# Anchor_PCB_V2.net
KiCad netlist of a schematic drawn in EAGLE
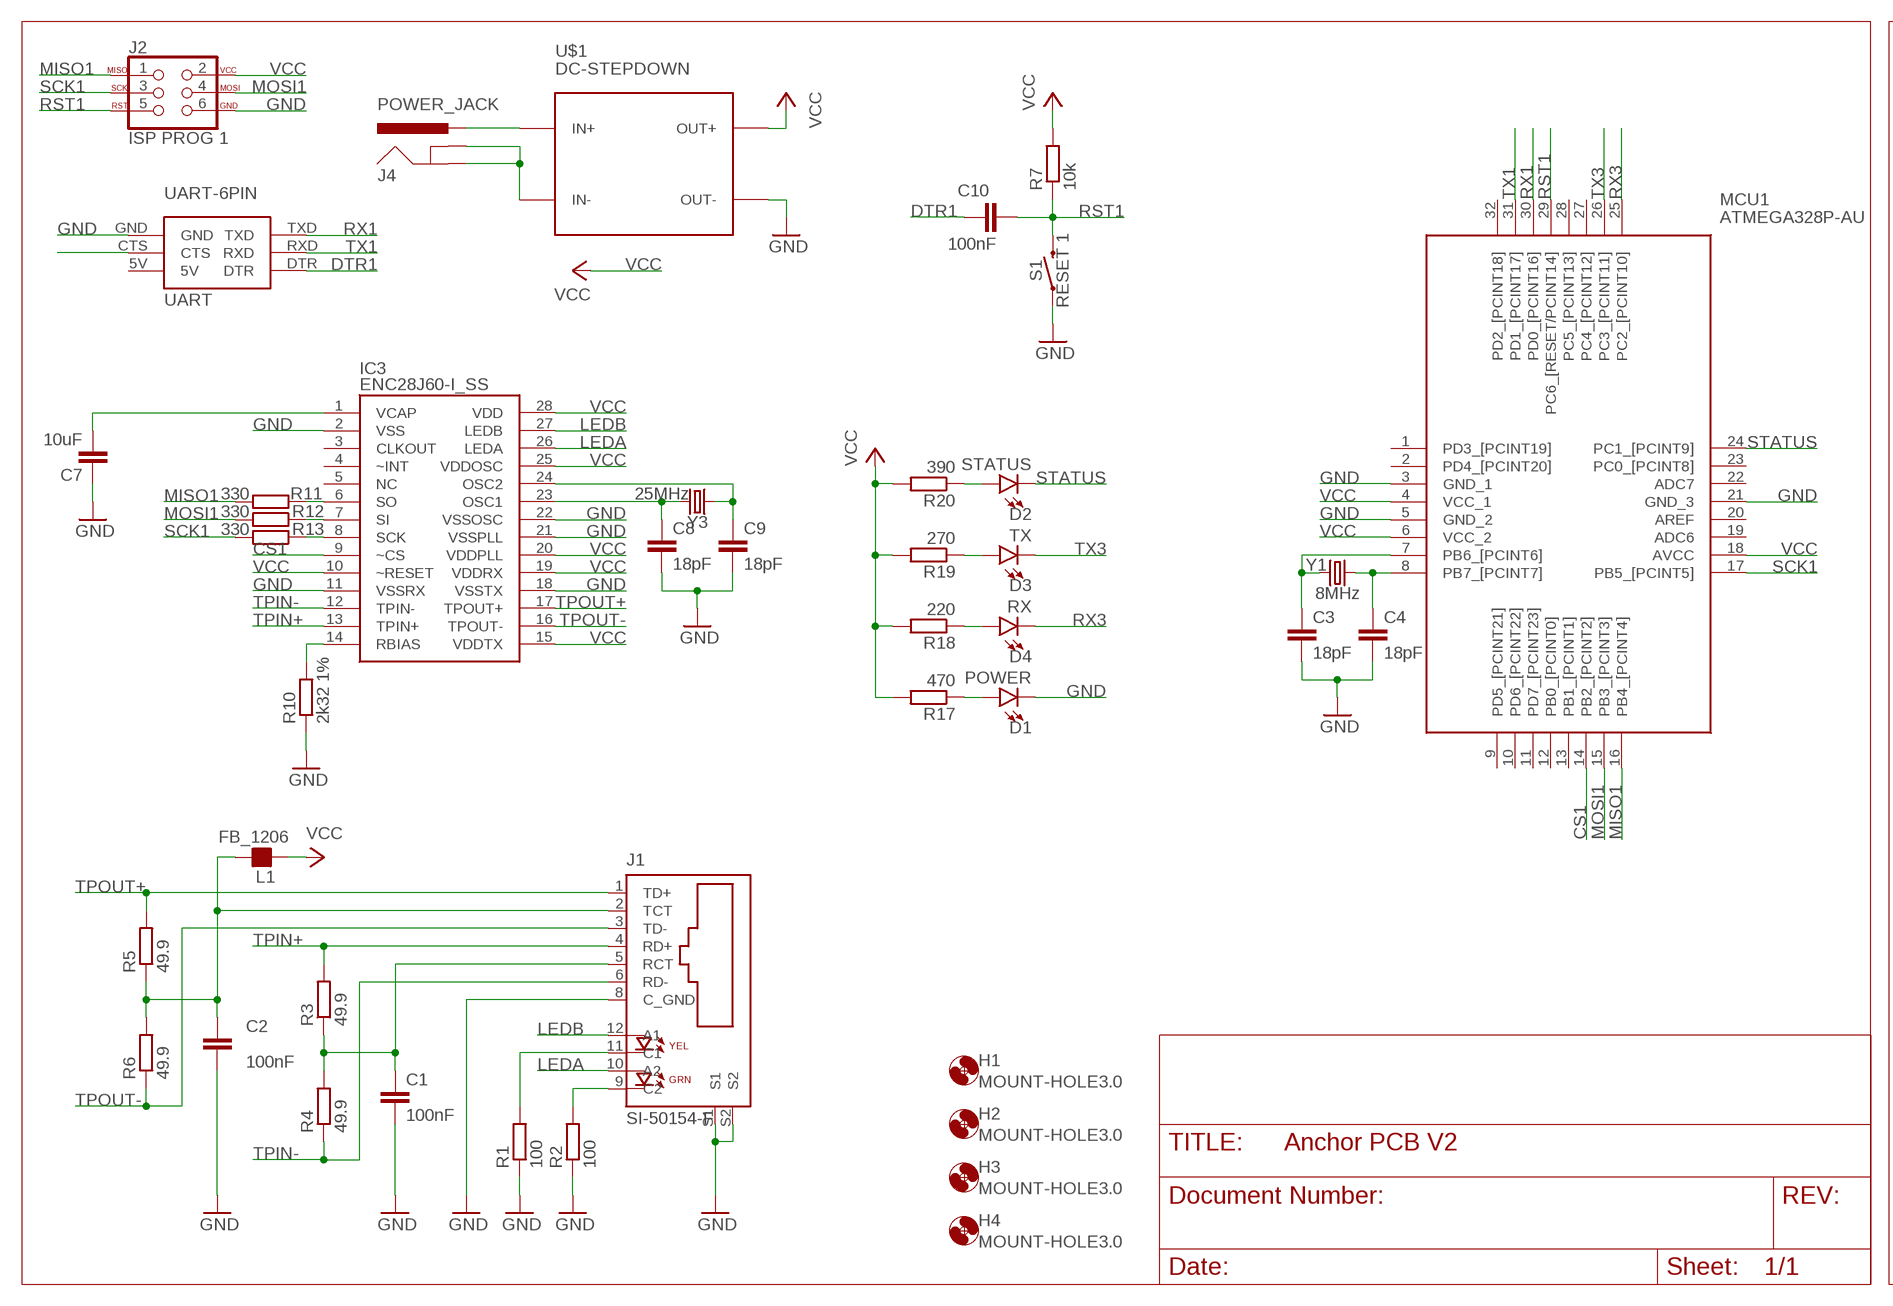
[diagram p0: schematic, sheet 1, part 1 of 2]
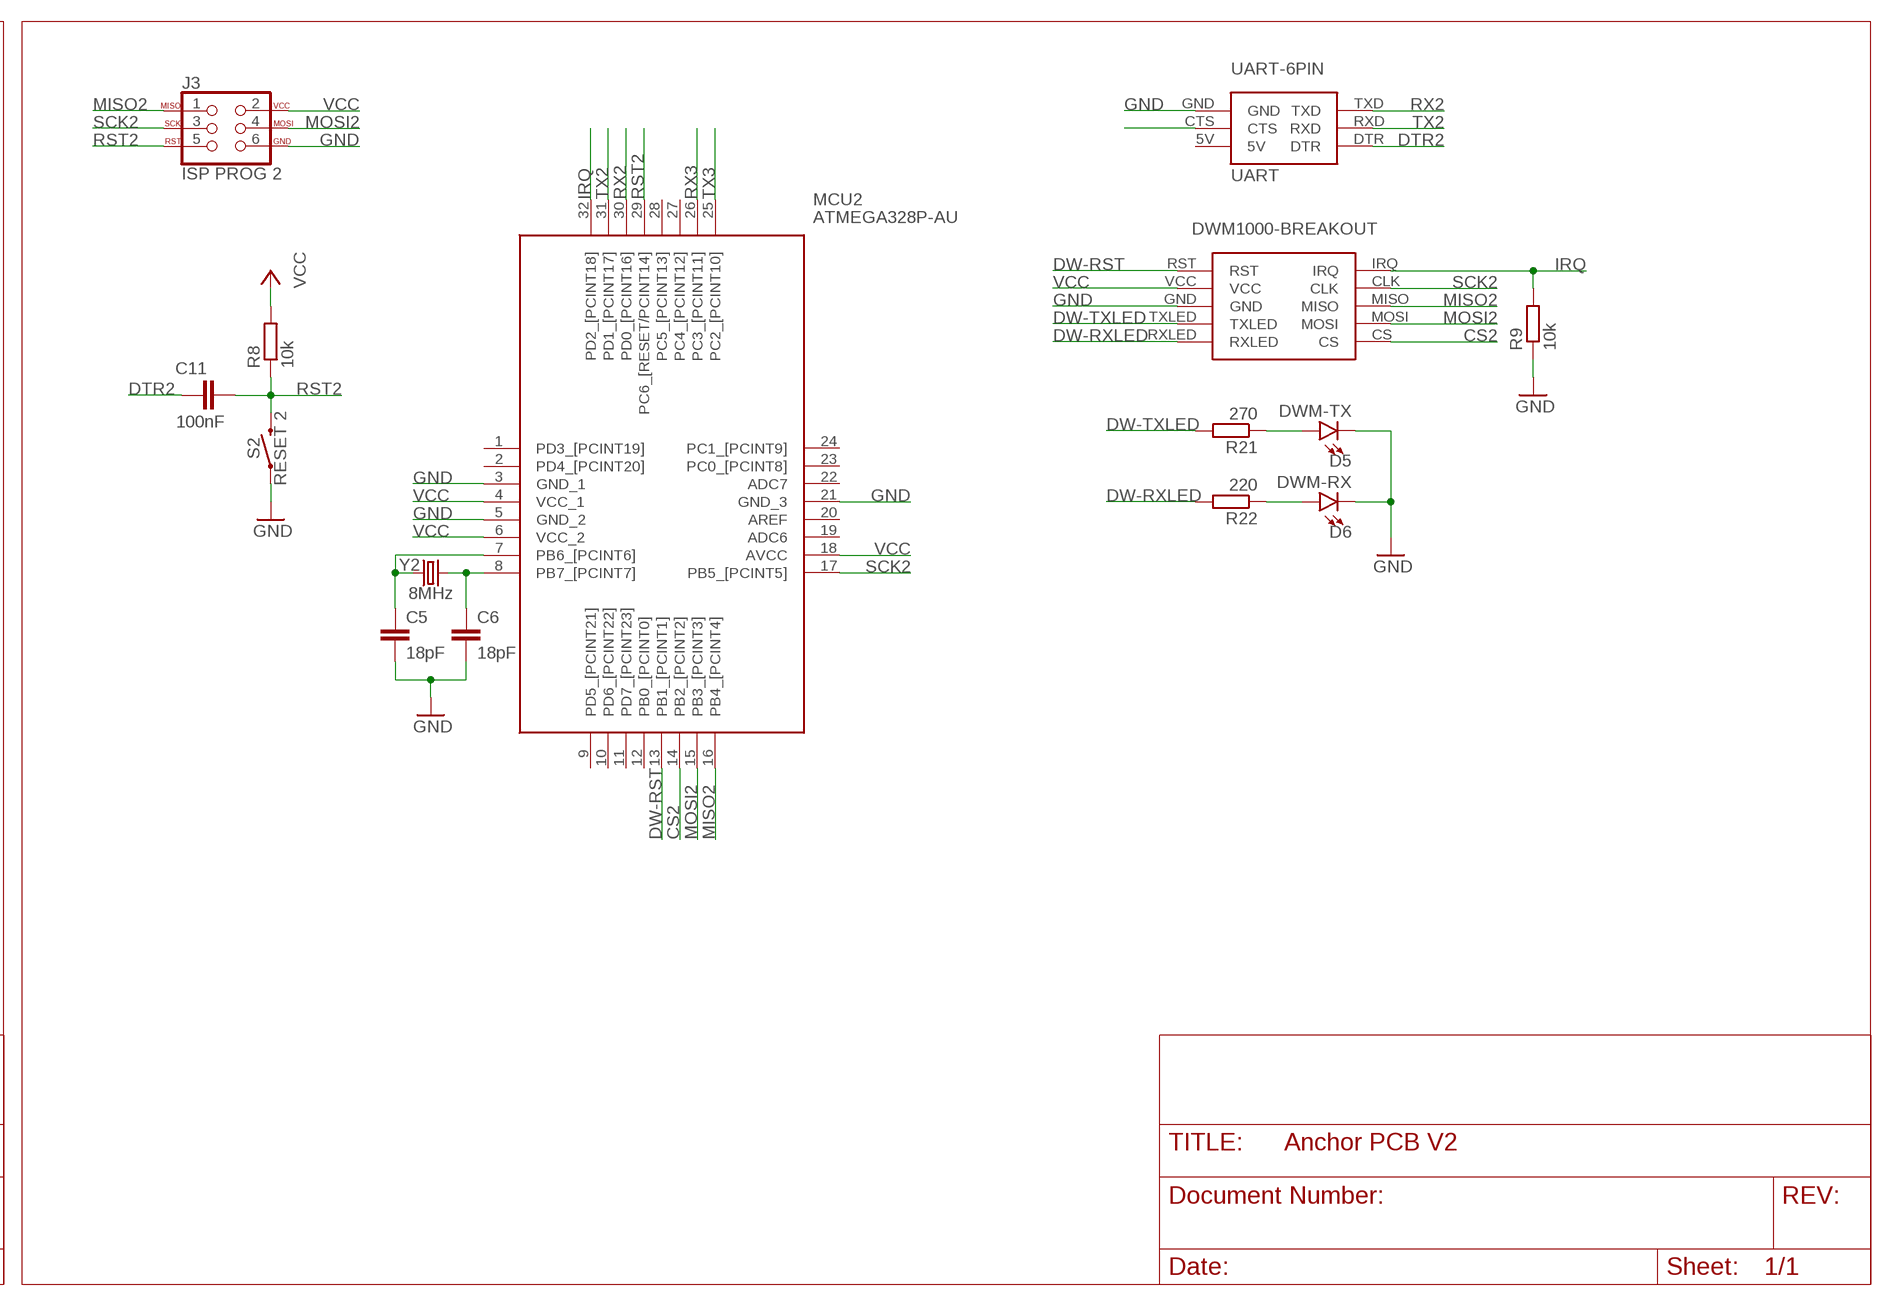
[diagram p1: schematic, sheet 1, part 2 of 2]

(export (version "E")
  (design (tool "Eeschema 10.0.6"))
  (components
    (comp (ref "C1")
      (value "100nF")
      (footprint "eagle-import:C0805")
      (libsource (lib "eagle-import") (part "C-EUC0805"))
    )
    (comp (ref "C2")
      (value "100nF")
      (footprint "eagle-import:C0805")
      (libsource (lib "eagle-import") (part "C-EUC0805"))
    )
    (comp (ref "C3")
      (value "18pF")
      (footprint "eagle-import:C0805")
      (libsource (lib "eagle-import") (part "C-EUC0805"))
    )
    (comp (ref "C4")
      (value "18pF")
      (footprint "eagle-import:C0805")
      (libsource (lib "eagle-import") (part "C-EUC0805"))
    )
    (comp (ref "C5")
      (value "18pF")
      (footprint "eagle-import:C0805")
      (libsource (lib "eagle-import") (part "C-EUC0805"))
    )
    (comp (ref "C6")
      (value "18pF")
      (footprint "eagle-import:C0805")
      (libsource (lib "eagle-import") (part "C-EUC0805"))
    )
    (comp (ref "C7")
      (value "10uF")
      (footprint "eagle-import:C0805")
      (libsource (lib "eagle-import") (part "C-EUC0805"))
    )
    (comp (ref "C8")
      (value "18pF")
      (footprint "eagle-import:C0805")
      (libsource (lib "eagle-import") (part "C-EUC0805"))
    )
    (comp (ref "C9")
      (value "18pF")
      (footprint "eagle-import:C0805")
      (libsource (lib "eagle-import") (part "C-EUC0805"))
    )
    (comp (ref "C10")
      (value "100nF")
      (footprint "eagle-import:C0805")
      (libsource (lib "eagle-import") (part "C-EUC0805"))
    )
    (comp (ref "C11")
      (value "100nF")
      (footprint "eagle-import:C0805")
      (libsource (lib "eagle-import") (part "C-EUC0805"))
    )
    (comp (ref "D1")
      (value "POWER")
      (footprint "eagle-import:LED-1206")
      (libsource (lib "eagle-import") (part "LED-BLUE1206"))
    )
    (comp (ref "D2")
      (value "STATUS")
      (footprint "eagle-import:LED-1206")
      (fields (field (name "SPICEPREFIX") "D"))
      (libsource (lib "eagle-import") (part "LED-RED1206"))
    )
    (comp (ref "D3")
      (value "TX")
      (footprint "eagle-import:LED-1206")
      (fields (field (name "SPICEPREFIX") "D"))
      (libsource (lib "eagle-import") (part "LED-YELLOWLILYPAD"))
    )
    (comp (ref "D4")
      (value "RX")
      (footprint "eagle-import:LED-1206")
      (fields (field (name "SPICEPREFIX") "D"))
      (libsource (lib "eagle-import") (part "LED-GREEN1206"))
    )
    (comp (ref "D5")
      (value "DWM-TX")
      (footprint "eagle-import:LED-1206")
      (fields (field (name "SPICEPREFIX") "D"))
      (libsource (lib "eagle-import") (part "LED-YELLOWLILYPAD"))
    )
    (comp (ref "D6")
      (value "DWM-RX")
      (footprint "eagle-import:LED-1206")
      (fields (field (name "SPICEPREFIX") "D"))
      (libsource (lib "eagle-import") (part "LED-GREEN1206"))
    )
    (comp (ref "H1")
      (value "MOUNT-HOLE3.0")
      (footprint "eagle-import:3,0")
      (libsource (lib "eagle-import") (part "MOUNT-HOLE3.0"))
    )
    (comp (ref "H2")
      (value "MOUNT-HOLE3.0")
      (footprint "eagle-import:3,0")
      (libsource (lib "eagle-import") (part "MOUNT-HOLE3.0"))
    )
    (comp (ref "H3")
      (value "MOUNT-HOLE3.0")
      (footprint "eagle-import:3,0")
      (libsource (lib "eagle-import") (part "MOUNT-HOLE3.0"))
    )
    (comp (ref "H4")
      (value "MOUNT-HOLE3.0")
      (footprint "eagle-import:3,0")
      (libsource (lib "eagle-import") (part "MOUNT-HOLE3.0"))
    )
    (comp (ref "IC3")
      (value "ENC28J60-I_SS")
      (footprint "eagle-import:SOP65P780X200-28N")
      (fields (field (name "ARROW_PART_NUMBER") "ENC28J60-I/SS") (field (name "RS_PART_NUMBER") "7707755P"))
      (libsource (lib "eagle-import") (part "ENC28J60-I_SS"))
    )
    (comp (ref "J1")
      (value "SI-50154-F")
      (footprint "eagle-import:STEWART_SI-50154-F")
      (fields (field (name "MF") "Stewart Connector"))
      (libsource (lib "eagle-import") (part "SI-50154-F"))
    )
    (comp (ref "J2")
      (value "ISP PROG 1")
      (footprint "eagle-import:2X3")
      (libsource (lib "eagle-import") (part "AVR_SPI_PROG_3X2PTH"))
    )
    (comp (ref "J3")
      (value "ISP PROG 2")
      (footprint "eagle-import:2X3")
      (libsource (lib "eagle-import") (part "AVR_SPI_PROG_3X2PTH"))
    )
    (comp (ref "J4")
      (value "POWER_JACK")
      (footprint "eagle-import:POWER_JACK_PTH")
      (libsource (lib "eagle-import") (part "POWER_JACK"))
    )
    (comp (ref "L1")
      (value "FB_1206")
      (footprint "eagle-import:L1206")
      (libsource (lib "eagle-import") (part "FB_1206"))
    )
    (comp (ref "MCU1")
      (value "ATMEGA328P-AU")
      (footprint "eagle-import:QFP80P900X900X120-32N")
      (fields (field (name "RS_PART_NUMBER") "1310271"))
      (libsource (lib "eagle-import") (part "ATMEGA328P-AU"))
    )
    (comp (ref "MCU2")
      (value "ATMEGA328P-AU")
      (footprint "eagle-import:QFP80P900X900X120-32N")
      (fields (field (name "RS_PART_NUMBER") "1310271"))
      (libsource (lib "eagle-import") (part "ATMEGA328P-AU"))
    )
    (comp (ref "R1")
      (value "100")
      (footprint "eagle-import:R0805")
      (libsource (lib "eagle-import") (part "R-EU_R0805"))
    )
    (comp (ref "R2")
      (value "100")
      (footprint "eagle-import:R0805")
      (libsource (lib "eagle-import") (part "R-EU_R0805"))
    )
    (comp (ref "R3")
      (value "49.9")
      (footprint "eagle-import:R1206")
      (libsource (lib "eagle-import") (part "R-EU_R1206"))
    )
    (comp (ref "R4")
      (value "49.9")
      (footprint "eagle-import:R1206")
      (libsource (lib "eagle-import") (part "R-EU_R1206"))
    )
    (comp (ref "R5")
      (value "49.9")
      (footprint "eagle-import:R1206")
      (libsource (lib "eagle-import") (part "R-EU_R1206"))
    )
    (comp (ref "R6")
      (value "49.9")
      (footprint "eagle-import:R1206")
      (libsource (lib "eagle-import") (part "R-EU_R1206"))
    )
    (comp (ref "R7")
      (value "10k")
      (footprint "eagle-import:R0805")
      (libsource (lib "eagle-import") (part "R-EU_R0805"))
    )
    (comp (ref "R8")
      (value "10k")
      (footprint "eagle-import:R0805")
      (libsource (lib "eagle-import") (part "R-EU_R0805"))
    )
    (comp (ref "R9")
      (value "10k")
      (footprint "eagle-import:R0805")
      (libsource (lib "eagle-import") (part "R-EU_R0805"))
    )
    (comp (ref "R10")
      (value "2k32 1%")
      (footprint "eagle-import:R1206")
      (libsource (lib "eagle-import") (part "R-EU_R1206"))
    )
    (comp (ref "R11")
      (value "330")
      (footprint "eagle-import:R0805")
      (libsource (lib "eagle-import") (part "R-EU_R0805"))
    )
    (comp (ref "R12")
      (value "330")
      (footprint "eagle-import:R0805")
      (libsource (lib "eagle-import") (part "R-EU_R0805"))
    )
    (comp (ref "R13")
      (value "330")
      (footprint "eagle-import:R0805")
      (libsource (lib "eagle-import") (part "R-EU_R0805"))
    )
    (comp (ref "R17")
      (value "470")
      (footprint "eagle-import:R1206")
      (libsource (lib "eagle-import") (part "R-EU_R1206"))
    )
    (comp (ref "R18")
      (value "220")
      (footprint "eagle-import:R1206")
      (libsource (lib "eagle-import") (part "R-EU_R1206"))
    )
    (comp (ref "R19")
      (value "270")
      (footprint "eagle-import:R1206")
      (libsource (lib "eagle-import") (part "R-EU_R1206"))
    )
    (comp (ref "R20")
      (value "390")
      (footprint "eagle-import:R1206")
      (libsource (lib "eagle-import") (part "R-EU_R1206"))
    )
    (comp (ref "R21")
      (value "270")
      (footprint "eagle-import:R1206")
      (libsource (lib "eagle-import") (part "R-EU_R1206"))
    )
    (comp (ref "R22")
      (value "220")
      (footprint "eagle-import:R1206")
      (libsource (lib "eagle-import") (part "R-EU_R1206"))
    )
    (comp (ref "S1")
      (value "RESET 1")
      (footprint "eagle-import:TACTILE_SWITCH_PTH_6.0MM")
      (libsource (lib "eagle-import") (part "MOMENTARY-SWITCH-SPST-PTH-6.0MM"))
    )
    (comp (ref "S2")
      (value "RESET 2")
      (footprint "eagle-import:TACTILE_SWITCH_PTH_6.0MM")
      (libsource (lib "eagle-import") (part "MOMENTARY-SWITCH-SPST-PTH-6.0MM"))
    )
    (comp (ref "U$1")
      (value "DC-STEPDOWN")
      (footprint "eagle-import:DC-DC-STEP-DOWN-LM2596")
      (libsource (lib "eagle-import") (part "DC-DC-STEP-DOWN-LM2596"))
    )
    (comp (ref "U$2")
      (value "DWM1000")
      (footprint "eagle-import:DWM1000-BREAKOUT")
      (libsource (lib "eagle-import") (part "DWM1000-BREAKOUT"))
    )
    (comp (ref "UART1")
      (value "UART1")
      (footprint "eagle-import:UART-6PIN")
      (libsource (lib "eagle-import") (part "UART-6PIN"))
    )
    (comp (ref "UART2")
      (value "UART2")
      (footprint "eagle-import:UART-6PIN")
      (libsource (lib "eagle-import") (part "UART-6PIN"))
    )
    (comp (ref "Y1")
      (value "8MHz")
      (footprint "eagle-import:HC49UP")
      (libsource (lib "eagle-import") (part "CRYSTALSMD-HC49UP"))
    )
    (comp (ref "Y2")
      (value "8MHz")
      (footprint "eagle-import:HC49UP")
      (libsource (lib "eagle-import") (part "CRYSTALSMD-HC49UP"))
    )
    (comp (ref "Y3")
      (value "25MHz")
      (footprint "eagle-import:HC49UP")
      (libsource (lib "eagle-import") (part "CRYSTALSMD-HC49UP"))
    )
  )
  (nets
    (net (code "1") (name "/CS1") (class "Default")
      (node (ref "IC3") (pin "9") (pinfunction "~{CS}_9") (pintype "bidirectional"))
      (node (ref "MCU1") (pin "14") (pinfunction "PB2_[PCINT2]_14") (pintype "bidirectional"))
    )
    (net (code "2") (name "/CS2") (class "Default")
      (node (ref "MCU2") (pin "14") (pinfunction "PB2_[PCINT2]_14") (pintype "bidirectional"))
      (node (ref "U$2") (pin "CS") (pinfunction "CS_CS") (pintype "bidirectional"))
    )
    (net (code "3") (name "/DTR1") (class "Default")
      (node (ref "C10") (pin "1") (pinfunction "1_1") (pintype "passive"))
      (node (ref "UART1") (pin "DTR") (pinfunction "DTR_DTR") (pintype "bidirectional"))
    )
    (net (code "4") (name "/DTR2") (class "Default")
      (node (ref "C11") (pin "1") (pinfunction "1_1") (pintype "passive"))
      (node (ref "UART2") (pin "DTR") (pinfunction "DTR_DTR") (pintype "bidirectional"))
    )
    (net (code "5") (name "/DW-RST") (class "Default")
      (node (ref "MCU2") (pin "13") (pinfunction "PB1_[PCINT1]_13") (pintype "bidirectional"))
      (node (ref "U$2") (pin "RST") (pinfunction "RST_RST") (pintype "bidirectional"))
    )
    (net (code "6") (name "/DW-RXLED") (class "Default")
      (node (ref "R22") (pin "2") (pinfunction "2_2") (pintype "passive"))
      (node (ref "U$2") (pin "RXLED") (pinfunction "RXLED_RXLED") (pintype "bidirectional"))
    )
    (net (code "7") (name "/DW-TXLED") (class "Default")
      (node (ref "R21") (pin "2") (pinfunction "2_2") (pintype "passive"))
      (node (ref "U$2") (pin "TXLED") (pinfunction "TXLED_TXLED") (pintype "bidirectional"))
    )
    (net (code "8") (name "/IRQ") (class "Default")
      (node (ref "MCU2") (pin "32") (pinfunction "PD2_[PCINT18]_32") (pintype "bidirectional"))
      (node (ref "R9") (pin "2") (pinfunction "2_2") (pintype "passive"))
      (node (ref "U$2") (pin "IRQ") (pinfunction "IRQ_IRQ") (pintype "bidirectional"))
    )
    (net (code "9") (name "/LEDA") (class "Default")
      (node (ref "IC3") (pin "26") (pinfunction "LEDA_26") (pintype "bidirectional"))
      (node (ref "J1") (pin "10") (pinfunction "A2_10") (pintype "passive"))
    )
    (net (code "10") (name "/LEDB") (class "Default")
      (node (ref "IC3") (pin "27") (pinfunction "LEDB_27") (pintype "bidirectional"))
      (node (ref "J1") (pin "12") (pinfunction "A1_12") (pintype "passive"))
    )
    (net (code "11") (name "/MISO1") (class "Default")
      (node (ref "J2") (pin "1") (pinfunction "1_1") (pintype "passive"))
      (node (ref "MCU1") (pin "16") (pinfunction "PB4_[PCINT4]_16") (pintype "bidirectional"))
      (node (ref "R11") (pin "2") (pinfunction "2_2") (pintype "passive"))
    )
    (net (code "12") (name "/MISO2") (class "Default")
      (node (ref "J3") (pin "1") (pinfunction "1_1") (pintype "passive"))
      (node (ref "MCU2") (pin "16") (pinfunction "PB4_[PCINT4]_16") (pintype "bidirectional"))
      (node (ref "U$2") (pin "MISO") (pinfunction "MISO_MISO") (pintype "bidirectional"))
    )
    (net (code "13") (name "/MOSI1") (class "Default")
      (node (ref "J2") (pin "4") (pinfunction "4_4") (pintype "passive"))
      (node (ref "MCU1") (pin "15") (pinfunction "PB3_[PCINT3]_15") (pintype "bidirectional"))
      (node (ref "R12") (pin "2") (pinfunction "2_2") (pintype "passive"))
    )
    (net (code "14") (name "/MOSI2") (class "Default")
      (node (ref "J3") (pin "4") (pinfunction "4_4") (pintype "passive"))
      (node (ref "MCU2") (pin "15") (pinfunction "PB3_[PCINT3]_15") (pintype "bidirectional"))
      (node (ref "U$2") (pin "MOSI") (pinfunction "MOSI_MOSI") (pintype "bidirectional"))
    )
    (net (code "15") (name "/RST1") (class "Default")
      (node (ref "C10") (pin "2") (pinfunction "2_2") (pintype "passive"))
      (node (ref "J2") (pin "5") (pinfunction "5_5") (pintype "passive"))
      (node (ref "MCU1") (pin "29") (pinfunction "PC6_[RESET/PCINT14]_29") (pintype "bidirectional"))
      (node (ref "R7") (pin "1") (pinfunction "1_1") (pintype "passive"))
      (node (ref "S1") (pin "3") (pinfunction "2_3") (pintype "passive"))
    )
    (net (code "16") (name "/RST2") (class "Default")
      (node (ref "C11") (pin "2") (pinfunction "2_2") (pintype "passive"))
      (node (ref "J3") (pin "5") (pinfunction "5_5") (pintype "passive"))
      (node (ref "MCU2") (pin "29") (pinfunction "PC6_[RESET/PCINT14]_29") (pintype "bidirectional"))
      (node (ref "R8") (pin "1") (pinfunction "1_1") (pintype "passive"))
      (node (ref "S2") (pin "3") (pinfunction "2_3") (pintype "passive"))
    )
    (net (code "17") (name "/RX1") (class "Default")
      (node (ref "MCU1") (pin "30") (pinfunction "PD0_[PCINT16]_30") (pintype "bidirectional"))
      (node (ref "UART1") (pin "TXD") (pinfunction "TXD_TXD") (pintype "bidirectional"))
    )
    (net (code "18") (name "/RX2") (class "Default")
      (node (ref "MCU2") (pin "30") (pinfunction "PD0_[PCINT16]_30") (pintype "bidirectional"))
      (node (ref "UART2") (pin "TXD") (pinfunction "TXD_TXD") (pintype "bidirectional"))
    )
    (net (code "19") (name "/RX3") (class "Default")
      (node (ref "D4") (pin "C") (pinfunction "C_C") (pintype "passive"))
      (node (ref "MCU1") (pin "25") (pinfunction "PC2_[PCINT10]_25") (pintype "bidirectional"))
      (node (ref "MCU2") (pin "26") (pinfunction "PC3_[PCINT11]_26") (pintype "bidirectional"))
    )
    (net (code "20") (name "/SCK1") (class "Default")
      (node (ref "J2") (pin "3") (pinfunction "3_3") (pintype "passive"))
      (node (ref "MCU1") (pin "17") (pinfunction "PB5_[PCINT5]_17") (pintype "bidirectional"))
      (node (ref "R13") (pin "2") (pinfunction "2_2") (pintype "passive"))
    )
    (net (code "21") (name "/SCK2") (class "Default")
      (node (ref "J3") (pin "3") (pinfunction "3_3") (pintype "passive"))
      (node (ref "MCU2") (pin "17") (pinfunction "PB5_[PCINT5]_17") (pintype "bidirectional"))
      (node (ref "U$2") (pin "CLK") (pinfunction "CLK_CLK") (pintype "bidirectional"))
    )
    (net (code "22") (name "/STATUS") (class "Default")
      (node (ref "D2") (pin "C") (pinfunction "C_C") (pintype "passive"))
      (node (ref "MCU1") (pin "24") (pinfunction "PC1_[PCINT9]_24") (pintype "bidirectional"))
    )
    (net (code "23") (name "/TPIN+") (class "Default")
      (node (ref "IC3") (pin "13") (pinfunction "TPIN+_13") (pintype "bidirectional"))
      (node (ref "J1") (pin "4") (pinfunction "RD+_4") (pintype "passive"))
      (node (ref "R3") (pin "2") (pinfunction "2_2") (pintype "passive"))
    )
    (net (code "24") (name "/TPIN-") (class "Default")
      (node (ref "IC3") (pin "12") (pinfunction "TPIN-_12") (pintype "bidirectional"))
      (node (ref "J1") (pin "6") (pinfunction "RD-_6") (pintype "passive"))
      (node (ref "R4") (pin "1") (pinfunction "1_1") (pintype "passive"))
    )
    (net (code "25") (name "/TPOUT+") (class "Default")
      (node (ref "IC3") (pin "17") (pinfunction "TPOUT+_17") (pintype "bidirectional"))
      (node (ref "J1") (pin "1") (pinfunction "TD+_1") (pintype "passive"))
      (node (ref "R5") (pin "2") (pinfunction "2_2") (pintype "passive"))
    )
    (net (code "26") (name "/TPOUT-") (class "Default")
      (node (ref "IC3") (pin "16") (pinfunction "TPOUT-_16") (pintype "bidirectional"))
      (node (ref "J1") (pin "3") (pinfunction "TD-_3") (pintype "passive"))
      (node (ref "R6") (pin "1") (pinfunction "1_1") (pintype "passive"))
    )
    (net (code "27") (name "/TX1") (class "Default")
      (node (ref "MCU1") (pin "31") (pinfunction "PD1_[PCINT17]_31") (pintype "bidirectional"))
      (node (ref "UART1") (pin "RXD") (pinfunction "RXD_RXD") (pintype "bidirectional"))
    )
    (net (code "28") (name "/TX2") (class "Default")
      (node (ref "MCU2") (pin "31") (pinfunction "PD1_[PCINT17]_31") (pintype "bidirectional"))
      (node (ref "UART2") (pin "RXD") (pinfunction "RXD_RXD") (pintype "bidirectional"))
    )
    (net (code "29") (name "/TX3") (class "Default")
      (node (ref "D3") (pin "C") (pinfunction "C_C") (pintype "passive"))
      (node (ref "MCU1") (pin "26") (pinfunction "PC3_[PCINT11]_26") (pintype "bidirectional"))
      (node (ref "MCU2") (pin "25") (pinfunction "PC2_[PCINT10]_25") (pintype "bidirectional"))
    )
    (net (code "30") (name "GND") (class "Default")
      (node (ref "C1") (pin "2") (pinfunction "2_2") (pintype "passive"))
      (node (ref "C2") (pin "2") (pinfunction "2_2") (pintype "passive"))
      (node (ref "C3") (pin "2") (pinfunction "2_2") (pintype "passive"))
      (node (ref "C4") (pin "2") (pinfunction "2_2") (pintype "passive"))
      (node (ref "C5") (pin "2") (pinfunction "2_2") (pintype "passive"))
      (node (ref "C6") (pin "2") (pinfunction "2_2") (pintype "passive"))
      (node (ref "C7") (pin "1") (pinfunction "1_1") (pintype "passive"))
      (node (ref "C8") (pin "2") (pinfunction "2_2") (pintype "passive"))
      (node (ref "C9") (pin "2") (pinfunction "2_2") (pintype "passive"))
      (node (ref "D1") (pin "C") (pinfunction "C_C") (pintype "passive"))
      (node (ref "D5") (pin "C") (pinfunction "C_C") (pintype "passive"))
      (node (ref "D6") (pin "C") (pinfunction "C_C") (pintype "passive"))
      (node (ref "IC3") (pin "11") (pinfunction "VSSRX_11") (pintype "bidirectional"))
      (node (ref "IC3") (pin "18") (pinfunction "VSSTX_18") (pintype "bidirectional"))
      (node (ref "IC3") (pin "2") (pinfunction "VSS_2") (pintype "bidirectional"))
      (node (ref "IC3") (pin "21") (pinfunction "VSSPLL_21") (pintype "bidirectional"))
      (node (ref "IC3") (pin "22") (pinfunction "VSSOSC_22") (pintype "bidirectional"))
      (node (ref "J1") (pin "8") (pinfunction "C_GND_8") (pintype "passive"))
      (node (ref "J1") (pin "S1") (pinfunction "S1_S1") (pintype "passive"))
      (node (ref "J1") (pin "S2") (pinfunction "S2_S2") (pintype "passive"))
      (node (ref "J2") (pin "6") (pinfunction "6_6") (pintype "passive"))
      (node (ref "J3") (pin "6") (pinfunction "6_6") (pintype "passive"))
      (node (ref "MCU1") (pin "21") (pinfunction "GND_3_21") (pintype "power_in"))
      (node (ref "MCU1") (pin "3") (pinfunction "GND_1_3") (pintype "power_in"))
      (node (ref "MCU1") (pin "5") (pinfunction "GND_2_5") (pintype "power_in"))
      (node (ref "MCU2") (pin "21") (pinfunction "GND_3_21") (pintype "power_in"))
      (node (ref "MCU2") (pin "3") (pinfunction "GND_1_3") (pintype "power_in"))
      (node (ref "MCU2") (pin "5") (pinfunction "GND_2_5") (pintype "power_in"))
      (node (ref "R1") (pin "1") (pinfunction "1_1") (pintype "passive"))
      (node (ref "R10") (pin "1") (pinfunction "1_1") (pintype "passive"))
      (node (ref "R2") (pin "1") (pinfunction "1_1") (pintype "passive"))
      (node (ref "R9") (pin "1") (pinfunction "1_1") (pintype "passive"))
      (node (ref "S1") (pin "1") (pinfunction "1_1") (pintype "passive"))
      (node (ref "S2") (pin "1") (pinfunction "1_1") (pintype "passive"))
      (node (ref "U$1") (pin "OUT-") (pinfunction "OUT-_OUT-") (pintype "bidirectional"))
      (node (ref "U$2") (pin "GND") (pinfunction "GND_GND") (pintype "bidirectional"))
      (node (ref "UART1") (pin "GND") (pinfunction "GND_GND") (pintype "bidirectional"))
      (node (ref "UART2") (pin "GND") (pinfunction "GND_GND") (pintype "bidirectional"))
    )
    (net (code "31") (name "Net-(D1-PadA)") (class "Default")
      (node (ref "D1") (pin "A") (pinfunction "A_A") (pintype "passive"))
      (node (ref "R17") (pin "1") (pinfunction "1_1") (pintype "passive"))
    )
    (net (code "32") (name "Net-(D2-PadA)") (class "Default")
      (node (ref "D2") (pin "A") (pinfunction "A_A") (pintype "passive"))
      (node (ref "R20") (pin "1") (pinfunction "1_1") (pintype "passive"))
    )
    (net (code "33") (name "Net-(D3-PadA)") (class "Default")
      (node (ref "D3") (pin "A") (pinfunction "A_A") (pintype "passive"))
      (node (ref "R19") (pin "1") (pinfunction "1_1") (pintype "passive"))
    )
    (net (code "34") (name "Net-(D4-PadA)") (class "Default")
      (node (ref "D4") (pin "A") (pinfunction "A_A") (pintype "passive"))
      (node (ref "R18") (pin "1") (pinfunction "1_1") (pintype "passive"))
    )
    (net (code "35") (name "Net-(D5-PadA)") (class "Default")
      (node (ref "D5") (pin "A") (pinfunction "A_A") (pintype "passive"))
      (node (ref "R21") (pin "1") (pinfunction "1_1") (pintype "passive"))
    )
    (net (code "36") (name "Net-(D6-PadA)") (class "Default")
      (node (ref "D6") (pin "A") (pinfunction "A_A") (pintype "passive"))
      (node (ref "R22") (pin "1") (pinfunction "1_1") (pintype "passive"))
    )
    (net (code "37") (name "Net-(IC3-OSC1)") (class "Default")
      (node (ref "C8") (pin "1") (pinfunction "1_1") (pintype "passive"))
      (node (ref "IC3") (pin "23") (pinfunction "OSC1_23") (pintype "bidirectional"))
      (node (ref "Y3") (pin "2") (pinfunction "2_2") (pintype "passive"))
    )
    (net (code "38") (name "Net-(IC3-OSC2)") (class "Default")
      (node (ref "C9") (pin "1") (pinfunction "1_1") (pintype "passive"))
      (node (ref "IC3") (pin "24") (pinfunction "OSC2_24") (pintype "bidirectional"))
      (node (ref "Y3") (pin "1") (pinfunction "1_1") (pintype "passive"))
    )
    (net (code "39") (name "Net-(IC3-RBIAS)") (class "Default")
      (node (ref "IC3") (pin "14") (pinfunction "RBIAS_14") (pintype "bidirectional"))
      (node (ref "R10") (pin "2") (pinfunction "2_2") (pintype "passive"))
    )
    (net (code "40") (name "Net-(IC3-SCK)") (class "Default")
      (node (ref "IC3") (pin "8") (pinfunction "SCK_8") (pintype "bidirectional"))
      (node (ref "R13") (pin "1") (pinfunction "1_1") (pintype "passive"))
    )
    (net (code "41") (name "Net-(IC3-SI)") (class "Default")
      (node (ref "IC3") (pin "7") (pinfunction "SI_7") (pintype "bidirectional"))
      (node (ref "R12") (pin "1") (pinfunction "1_1") (pintype "passive"))
    )
    (net (code "42") (name "Net-(IC3-SO)") (class "Default")
      (node (ref "IC3") (pin "6") (pinfunction "SO_6") (pintype "bidirectional"))
      (node (ref "R11") (pin "1") (pinfunction "1_1") (pintype "passive"))
    )
    (net (code "43") (name "Net-(IC3-VCAP)") (class "Default")
      (node (ref "C7") (pin "2") (pinfunction "2_2") (pintype "passive"))
      (node (ref "IC3") (pin "1") (pinfunction "VCAP_1") (pintype "bidirectional"))
    )
    (net (code "44") (name "Net-(J1-C1)") (class "Default")
      (node (ref "J1") (pin "11") (pinfunction "C1_11") (pintype "passive"))
      (node (ref "R1") (pin "2") (pinfunction "2_2") (pintype "passive"))
    )
    (net (code "45") (name "Net-(J1-C2)") (class "Default")
      (node (ref "J1") (pin "9") (pinfunction "C2_9") (pintype "passive"))
      (node (ref "R2") (pin "2") (pinfunction "2_2") (pintype "passive"))
    )
    (net (code "46") (name "Net-(J1-RCT)") (class "Default")
      (node (ref "C1") (pin "1") (pinfunction "1_1") (pintype "passive"))
      (node (ref "J1") (pin "5") (pinfunction "RCT_5") (pintype "passive"))
      (node (ref "R3") (pin "1") (pinfunction "1_1") (pintype "passive"))
      (node (ref "R4") (pin "2") (pinfunction "2_2") (pintype "passive"))
    )
    (net (code "47") (name "Net-(J1-TCT)") (class "Default")
      (node (ref "C2") (pin "1") (pinfunction "1_1") (pintype "passive"))
      (node (ref "J1") (pin "2") (pinfunction "TCT_2") (pintype "passive"))
      (node (ref "L1") (pin "2") (pinfunction "2_2") (pintype "passive"))
      (node (ref "R5") (pin "1") (pinfunction "1_1") (pintype "passive"))
      (node (ref "R6") (pin "2") (pinfunction "2_2") (pintype "passive"))
    )
    (net (code "48") (name "Net-(J4-PadGND)") (class "Default")
      (node (ref "J4") (pin "GND") (pinfunction "GND_GND") (pintype "bidirectional"))
      (node (ref "J4") (pin "GNDBREAK") (pinfunction "GNDBREAK_GNDBREAK") (pintype "bidirectional"))
      (node (ref "U$1") (pin "IN-") (pinfunction "IN-_IN-") (pintype "bidirectional"))
    )
    (net (code "49") (name "Net-(J4-PadPWR)") (class "Default")
      (node (ref "J4") (pin "PWR") (pinfunction "PWR_PWR") (pintype "bidirectional"))
      (node (ref "U$1") (pin "IN+") (pinfunction "IN+_IN+") (pintype "bidirectional"))
    )
    (net (code "50") (name "Net-(MCU1-PB6_[PCINT6])") (class "Default")
      (node (ref "C3") (pin "1") (pinfunction "1_1") (pintype "passive"))
      (node (ref "MCU1") (pin "7") (pinfunction "PB6_[PCINT6]_7") (pintype "bidirectional"))
      (node (ref "Y1") (pin "2") (pinfunction "2_2") (pintype "passive"))
    )
    (net (code "51") (name "Net-(MCU1-PB7_[PCINT7])") (class "Default")
      (node (ref "C4") (pin "1") (pinfunction "1_1") (pintype "passive"))
      (node (ref "MCU1") (pin "8") (pinfunction "PB7_[PCINT7]_8") (pintype "bidirectional"))
      (node (ref "Y1") (pin "1") (pinfunction "1_1") (pintype "passive"))
    )
    (net (code "52") (name "Net-(MCU2-PB6_[PCINT6])") (class "Default")
      (node (ref "C5") (pin "1") (pinfunction "1_1") (pintype "passive"))
      (node (ref "MCU2") (pin "7") (pinfunction "PB6_[PCINT6]_7") (pintype "bidirectional"))
      (node (ref "Y2") (pin "1") (pinfunction "1_1") (pintype "passive"))
    )
    (net (code "53") (name "Net-(MCU2-PB7_[PCINT7])") (class "Default")
      (node (ref "C6") (pin "1") (pinfunction "1_1") (pintype "passive"))
      (node (ref "MCU2") (pin "8") (pinfunction "PB7_[PCINT7]_8") (pintype "bidirectional"))
      (node (ref "Y2") (pin "2") (pinfunction "2_2") (pintype "passive"))
    )
    (net (code "54") (name "VCC") (class "Default")
      (node (ref "IC3") (pin "10") (pinfunction "~{RESET}_10") (pintype "bidirectional"))
      (node (ref "IC3") (pin "15") (pinfunction "VDDTX_15") (pintype "bidirectional"))
      (node (ref "IC3") (pin "19") (pinfunction "VDDRX_19") (pintype "bidirectional"))
      (node (ref "IC3") (pin "20") (pinfunction "VDDPLL_20") (pintype "bidirectional"))
      (node (ref "IC3") (pin "25") (pinfunction "VDDOSC_25") (pintype "bidirectional"))
      (node (ref "IC3") (pin "28") (pinfunction "VDD_28") (pintype "bidirectional"))
      (node (ref "J2") (pin "2") (pinfunction "2_2") (pintype "passive"))
      (node (ref "J3") (pin "2") (pinfunction "2_2") (pintype "passive"))
      (node (ref "L1") (pin "1") (pinfunction "1_1") (pintype "passive"))
      (node (ref "MCU1") (pin "18") (pinfunction "AVCC_18") (pintype "power_in"))
      (node (ref "MCU1") (pin "4") (pinfunction "VCC_1_4") (pintype "power_in"))
      (node (ref "MCU1") (pin "6") (pinfunction "VCC_2_6") (pintype "power_in"))
      (node (ref "MCU2") (pin "18") (pinfunction "AVCC_18") (pintype "power_in"))
      (node (ref "MCU2") (pin "4") (pinfunction "VCC_1_4") (pintype "power_in"))
      (node (ref "MCU2") (pin "6") (pinfunction "VCC_2_6") (pintype "power_in"))
      (node (ref "R17") (pin "2") (pinfunction "2_2") (pintype "passive"))
      (node (ref "R18") (pin "2") (pinfunction "2_2") (pintype "passive"))
      (node (ref "R19") (pin "2") (pinfunction "2_2") (pintype "passive"))
      (node (ref "R20") (pin "2") (pinfunction "2_2") (pintype "passive"))
      (node (ref "R7") (pin "2") (pinfunction "2_2") (pintype "passive"))
      (node (ref "R8") (pin "2") (pinfunction "2_2") (pintype "passive"))
      (node (ref "U$1") (pin "OUT+") (pinfunction "OUT+_OUT+") (pintype "bidirectional"))
      (node (ref "U$2") (pin "VCC") (pinfunction "VCC_VCC") (pintype "bidirectional"))
    )
    (net (code "55") (name "unconnected-(IC3-CLKOUT-Pad3)") (class "Default")
      (node (ref "IC3") (pin "3") (pinfunction "CLKOUT_3") (pintype "bidirectional"))
    )
    (net (code "56") (name "unconnected-(IC3-NC-Pad5)") (class "Default")
      (node (ref "IC3") (pin "5") (pinfunction "NC_5") (pintype "no_connect"))
    )
    (net (code "57") (name "unconnected-(IC3-~{INT}-Pad4)") (class "Default")
      (node (ref "IC3") (pin "4") (pinfunction "~{INT}_4") (pintype "bidirectional"))
    )
    (net (code "58") (name "unconnected-(MCU1-ADC6-Pad19)") (class "Default")
      (node (ref "MCU1") (pin "19") (pinfunction "ADC6_19") (pintype "bidirectional"))
    )
    (net (code "59") (name "unconnected-(MCU1-ADC7-Pad22)") (class "Default")
      (node (ref "MCU1") (pin "22") (pinfunction "ADC7_22") (pintype "bidirectional"))
    )
    (net (code "60") (name "unconnected-(MCU1-AREF-Pad20)") (class "Default")
      (node (ref "MCU1") (pin "20") (pinfunction "AREF_20") (pintype "bidirectional"))
    )
    (net (code "61") (name "unconnected-(MCU1-PB0_[PCINT0]-Pad12)") (class "Default")
      (node (ref "MCU1") (pin "12") (pinfunction "PB0_[PCINT0]_12") (pintype "bidirectional"))
    )
    (net (code "62") (name "unconnected-(MCU1-PB1_[PCINT1]-Pad13)") (class "Default")
      (node (ref "MCU1") (pin "13") (pinfunction "PB1_[PCINT1]_13") (pintype "bidirectional"))
    )
    (net (code "63") (name "unconnected-(MCU1-PC0_[PCINT8]-Pad23)") (class "Default")
      (node (ref "MCU1") (pin "23") (pinfunction "PC0_[PCINT8]_23") (pintype "bidirectional"))
    )
    (net (code "64") (name "unconnected-(MCU1-PC4_[PCINT12]-Pad27)") (class "Default")
      (node (ref "MCU1") (pin "27") (pinfunction "PC4_[PCINT12]_27") (pintype "bidirectional"))
    )
    (net (code "65") (name "unconnected-(MCU1-PC5_[PCINT13]-Pad28)") (class "Default")
      (node (ref "MCU1") (pin "28") (pinfunction "PC5_[PCINT13]_28") (pintype "bidirectional"))
    )
    (net (code "66") (name "unconnected-(MCU1-PD2_[PCINT18]-Pad32)") (class "Default")
      (node (ref "MCU1") (pin "32") (pinfunction "PD2_[PCINT18]_32") (pintype "bidirectional"))
    )
    (net (code "67") (name "unconnected-(MCU1-PD3_[PCINT19]-Pad1)") (class "Default")
      (node (ref "MCU1") (pin "1") (pinfunction "PD3_[PCINT19]_1") (pintype "bidirectional"))
    )
    (net (code "68") (name "unconnected-(MCU1-PD4_[PCINT20]-Pad2)") (class "Default")
      (node (ref "MCU1") (pin "2") (pinfunction "PD4_[PCINT20]_2") (pintype "bidirectional"))
    )
    (net (code "69") (name "unconnected-(MCU1-PD5_[PCINT21]-Pad9)") (class "Default")
      (node (ref "MCU1") (pin "9") (pinfunction "PD5_[PCINT21]_9") (pintype "bidirectional"))
    )
    (net (code "70") (name "unconnected-(MCU1-PD6_[PCINT22]-Pad10)") (class "Default")
      (node (ref "MCU1") (pin "10") (pinfunction "PD6_[PCINT22]_10") (pintype "bidirectional"))
    )
    (net (code "71") (name "unconnected-(MCU1-PD7_[PCINT23]-Pad11)") (class "Default")
      (node (ref "MCU1") (pin "11") (pinfunction "PD7_[PCINT23]_11") (pintype "bidirectional"))
    )
    (net (code "72") (name "unconnected-(MCU2-ADC6-Pad19)") (class "Default")
      (node (ref "MCU2") (pin "19") (pinfunction "ADC6_19") (pintype "bidirectional"))
    )
    (net (code "73") (name "unconnected-(MCU2-ADC7-Pad22)") (class "Default")
      (node (ref "MCU2") (pin "22") (pinfunction "ADC7_22") (pintype "bidirectional"))
    )
    (net (code "74") (name "unconnected-(MCU2-AREF-Pad20)") (class "Default")
      (node (ref "MCU2") (pin "20") (pinfunction "AREF_20") (pintype "bidirectional"))
    )
    (net (code "75") (name "unconnected-(MCU2-PB0_[PCINT0]-Pad12)") (class "Default")
      (node (ref "MCU2") (pin "12") (pinfunction "PB0_[PCINT0]_12") (pintype "bidirectional"))
    )
    (net (code "76") (name "unconnected-(MCU2-PC0_[PCINT8]-Pad23)") (class "Default")
      (node (ref "MCU2") (pin "23") (pinfunction "PC0_[PCINT8]_23") (pintype "bidirectional"))
    )
    (net (code "77") (name "unconnected-(MCU2-PC1_[PCINT9]-Pad24)") (class "Default")
      (node (ref "MCU2") (pin "24") (pinfunction "PC1_[PCINT9]_24") (pintype "bidirectional"))
    )
    (net (code "78") (name "unconnected-(MCU2-PC4_[PCINT12]-Pad27)") (class "Default")
      (node (ref "MCU2") (pin "27") (pinfunction "PC4_[PCINT12]_27") (pintype "bidirectional"))
    )
    (net (code "79") (name "unconnected-(MCU2-PC5_[PCINT13]-Pad28)") (class "Default")
      (node (ref "MCU2") (pin "28") (pinfunction "PC5_[PCINT13]_28") (pintype "bidirectional"))
    )
    (net (code "80") (name "unconnected-(MCU2-PD3_[PCINT19]-Pad1)") (class "Default")
      (node (ref "MCU2") (pin "1") (pinfunction "PD3_[PCINT19]_1") (pintype "bidirectional"))
    )
    (net (code "81") (name "unconnected-(MCU2-PD4_[PCINT20]-Pad2)") (class "Default")
      (node (ref "MCU2") (pin "2") (pinfunction "PD4_[PCINT20]_2") (pintype "bidirectional"))
    )
    (net (code "82") (name "unconnected-(MCU2-PD5_[PCINT21]-Pad9)") (class "Default")
      (node (ref "MCU2") (pin "9") (pinfunction "PD5_[PCINT21]_9") (pintype "bidirectional"))
    )
    (net (code "83") (name "unconnected-(MCU2-PD6_[PCINT22]-Pad10)") (class "Default")
      (node (ref "MCU2") (pin "10") (pinfunction "PD6_[PCINT22]_10") (pintype "bidirectional"))
    )
    (net (code "84") (name "unconnected-(MCU2-PD7_[PCINT23]-Pad11)") (class "Default")
      (node (ref "MCU2") (pin "11") (pinfunction "PD7_[PCINT23]_11") (pintype "bidirectional"))
    )
    (net (code "85") (name "unconnected-(UART1-Pad5V)") (class "Default")
      (node (ref "UART1") (pin "5V") (pinfunction "5V_5V") (pintype "bidirectional"))
    )
    (net (code "86") (name "unconnected-(UART1-PadCTS)") (class "Default")
      (node (ref "UART1") (pin "CTS") (pinfunction "CTS_CTS") (pintype "bidirectional"))
    )
    (net (code "87") (name "unconnected-(UART2-Pad5V)") (class "Default")
      (node (ref "UART2") (pin "5V") (pinfunction "5V_5V") (pintype "bidirectional"))
    )
    (net (code "88") (name "unconnected-(UART2-PadCTS)") (class "Default")
      (node (ref "UART2") (pin "CTS") (pinfunction "CTS_CTS") (pintype "bidirectional"))
    )
  )
)
